# STM32H730_PINOUT.net
KiCad netlist of a schematic drawn in Altium Designer
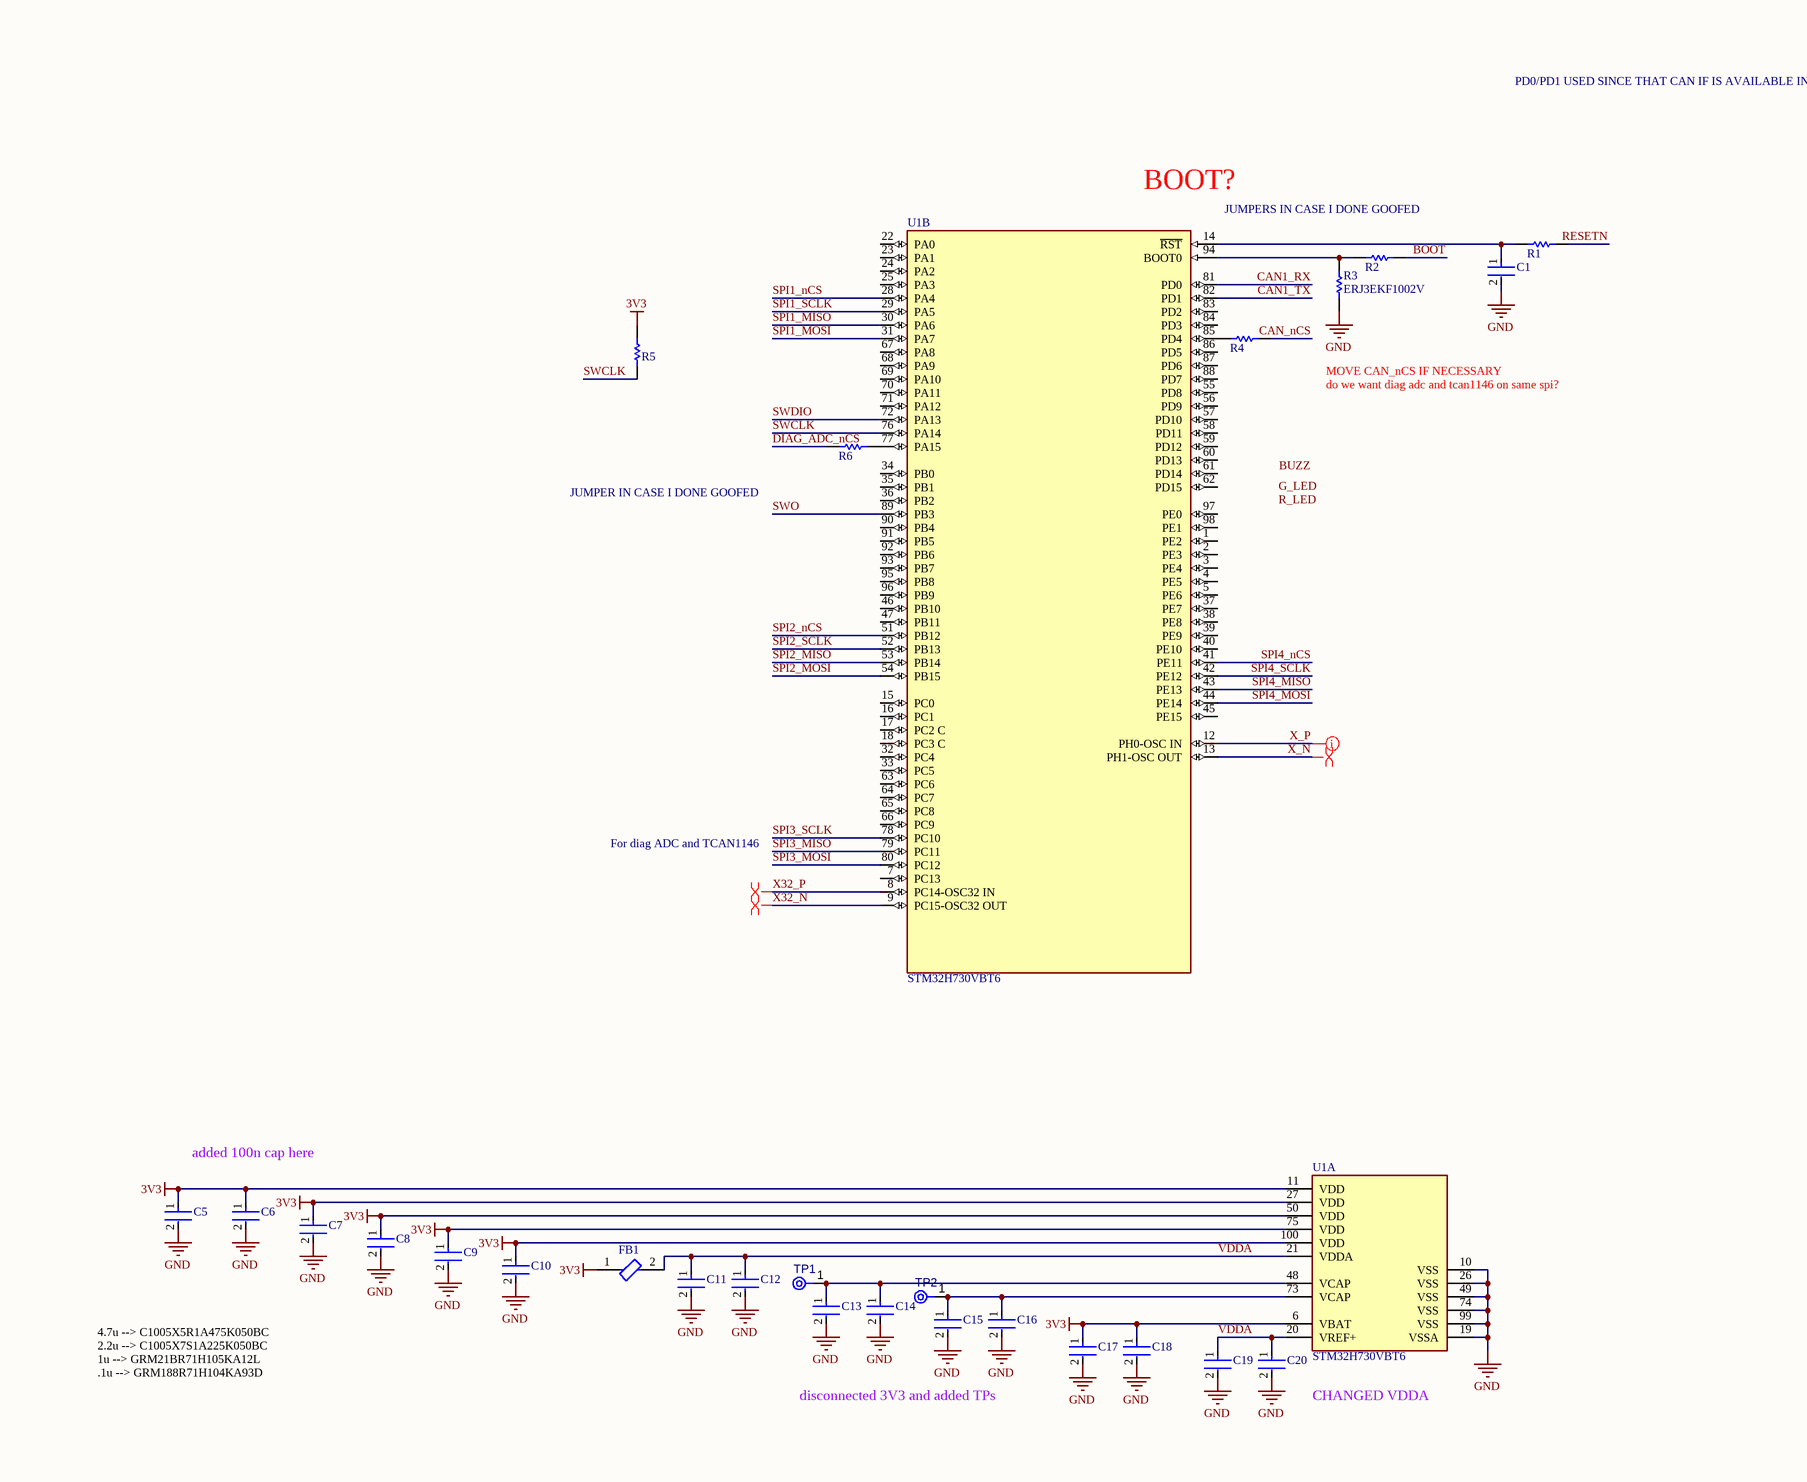
[diagram p0: STM32H730_PINOUT.SchDoc, top left]
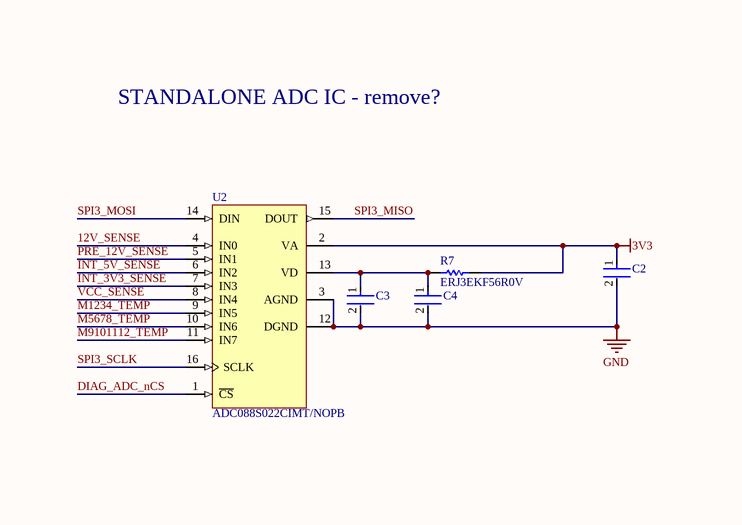
[diagram p1: STM32H730_PINOUT.SchDoc, top middle]
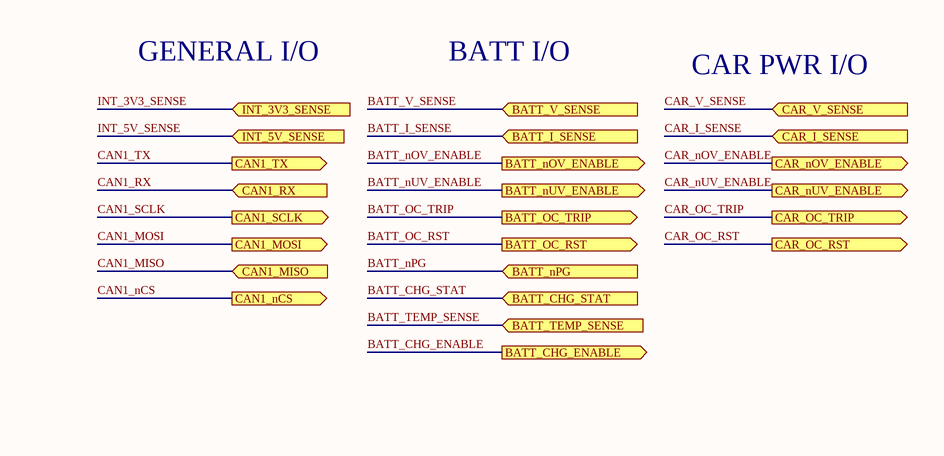
[diagram p2: STM32H730_PINOUT.SchDoc, top right]
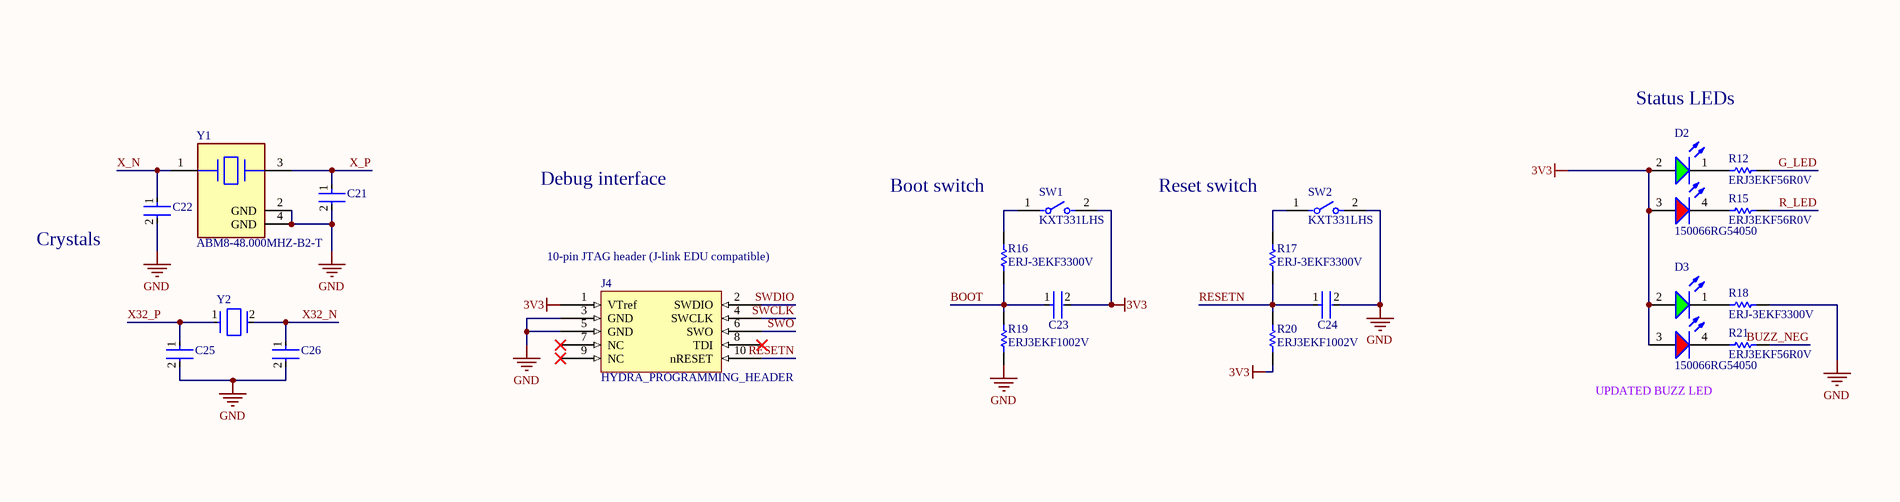
[diagram p3: STM32H730_PINOUT.SchDoc, bottom left]
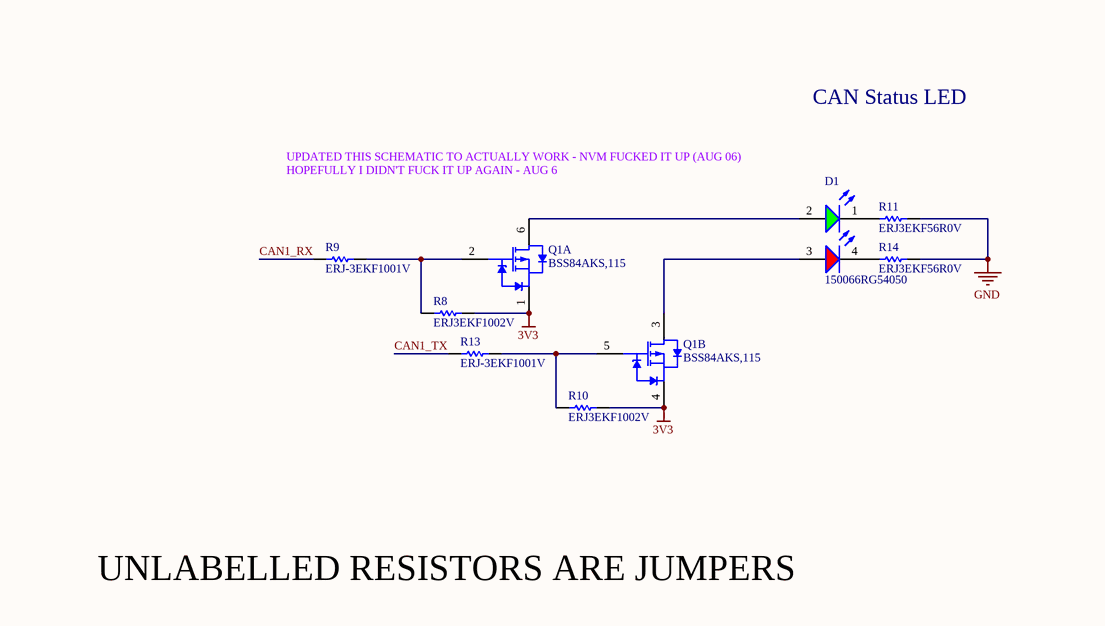
[diagram p4: STM32H730_PINOUT.SchDoc, bottom right]

(export (version "E")
  (design (tool "Eeschema 10.0.6"))
  (components
    (comp (ref "C1")
      (value "100n 10v")
      (footprint "FP-0402-L_1_0_0_05-W_0_5-IPC_A")
      (description "LARGE PADS, 0402 CAP, CHANGE COMMENT TO MATCH REAL P/N")
      (libsource (lib "Space Concordia") (part "b4654b650e69147ec39a6b967a45e02"))
    )
    (comp (ref "C2")
      (value "100n 10v")
      (footprint "FP-0402-L_1_0_0_05-W_0_5-IPC_A")
      (description "LARGE PADS, 0402 CAP, CHANGE COMMENT TO MATCH REAL P/N")
      (libsource (lib "Space Concordia") (part "b4654b650e69147ec39a6b967a45e02"))
    )
    (comp (ref "C3")
      (value "100n 10v")
      (footprint "FP-0402-L_1_0_0_05-W_0_5-IPC_A")
      (description "LARGE PADS, 0402 CAP, CHANGE COMMENT TO MATCH REAL P/N")
      (libsource (lib "Space Concordia") (part "b4654b650e69147ec39a6b967a45e02"))
    )
    (comp (ref "C4")
      (value "100n 10v")
      (footprint "FP-0402-L_1_0_0_05-W_0_5-IPC_A")
      (description "LARGE PADS, 0402 CAP, CHANGE COMMENT TO MATCH REAL P/N")
      (libsource (lib "Space Concordia") (part "b4654b650e69147ec39a6b967a45e02"))
    )
    (comp (ref "C5")
      (value "4.7u 10v")
      (footprint "FP-0402-L_1_0_0_05-W_0_5-IPC_A")
      (description "LARGE PADS, 0402 CAP, CHANGE COMMENT TO MATCH REAL P/N")
      (libsource (lib "Space Concordia") (part "b4654b650e69147ec39a6b967a45e02"))
    )
    (comp (ref "C6")
      (value "100n 10v")
      (footprint "FP-0402-L_1_0_0_05-W_0_5-IPC_A")
      (description "LARGE PADS, 0402 CAP, CHANGE COMMENT TO MATCH REAL P/N")
      (libsource (lib "Space Concordia") (part "b4654b650e69147ec39a6b967a45e02"))
    )
    (comp (ref "C7")
      (value "100n 10v")
      (footprint "FP-0402-L_1_0_0_05-W_0_5-IPC_A")
      (description "LARGE PADS, 0402 CAP, CHANGE COMMENT TO MATCH REAL P/N")
      (libsource (lib "Space Concordia") (part "b4654b650e69147ec39a6b967a45e02"))
    )
    (comp (ref "C8")
      (value "100n 10v")
      (footprint "FP-0402-L_1_0_0_05-W_0_5-IPC_A")
      (description "LARGE PADS, 0402 CAP, CHANGE COMMENT TO MATCH REAL P/N")
      (libsource (lib "Space Concordia") (part "b4654b650e69147ec39a6b967a45e02"))
    )
    (comp (ref "C9")
      (value "100n 10v")
      (footprint "FP-0402-L_1_0_0_05-W_0_5-IPC_A")
      (description "LARGE PADS, 0402 CAP, CHANGE COMMENT TO MATCH REAL P/N")
      (libsource (lib "Space Concordia") (part "b4654b650e69147ec39a6b967a45e02"))
    )
    (comp (ref "C10")
      (value "100n 10v")
      (footprint "FP-0402-L_1_0_0_05-W_0_5-IPC_A")
      (description "LARGE PADS, 0402 CAP, CHANGE COMMENT TO MATCH REAL P/N")
      (libsource (lib "Space Concordia") (part "b4654b650e69147ec39a6b967a45e02"))
    )
    (comp (ref "C11")
      (value "1u 10v")
      (footprint "FP-0402-L_1_0_0_05-W_0_5-IPC_A")
      (description "LARGE PADS, 0402 CAP, CHANGE COMMENT TO MATCH REAL P/N")
      (libsource (lib "Space Concordia") (part "b4654b650e69147ec39a6b967a45e02"))
    )
    (comp (ref "C12")
      (value "100n 10v")
      (footprint "FP-0402-L_1_0_0_05-W_0_5-IPC_A")
      (description "LARGE PADS, 0402 CAP, CHANGE COMMENT TO MATCH REAL P/N")
      (libsource (lib "Space Concordia") (part "b4654b650e69147ec39a6b967a45e02"))
    )
    (comp (ref "C13")
      (value "2.2u 10v")
      (footprint "FP-0402-L_1_0_0_05-W_0_5-IPC_A")
      (description "LARGE PADS, 0402 CAP, CHANGE COMMENT TO MATCH REAL P/N")
      (libsource (lib "Space Concordia") (part "b4654b650e69147ec39a6b967a45e02"))
    )
    (comp (ref "C14")
      (value "100n 10v")
      (footprint "FP-0402-L_1_0_0_05-W_0_5-IPC_A")
      (description "LARGE PADS, 0402 CAP, CHANGE COMMENT TO MATCH REAL P/N")
      (libsource (lib "Space Concordia") (part "b4654b650e69147ec39a6b967a45e02"))
    )
    (comp (ref "C15")
      (value "2.2u 10v")
      (footprint "FP-0402-L_1_0_0_05-W_0_5-IPC_A")
      (description "LARGE PADS, 0402 CAP, CHANGE COMMENT TO MATCH REAL P/N")
      (libsource (lib "Space Concordia") (part "b4654b650e69147ec39a6b967a45e02"))
    )
    (comp (ref "C16")
      (value "100n 10v")
      (footprint "FP-0402-L_1_0_0_05-W_0_5-IPC_A")
      (description "LARGE PADS, 0402 CAP, CHANGE COMMENT TO MATCH REAL P/N")
      (libsource (lib "Space Concordia") (part "b4654b650e69147ec39a6b967a45e02"))
    )
    (comp (ref "C17")
      (value "1u 10v")
      (footprint "FP-0402-L_1_0_0_05-W_0_5-IPC_A")
      (description "LARGE PADS, 0402 CAP, CHANGE COMMENT TO MATCH REAL P/N")
      (libsource (lib "Space Concordia") (part "b4654b650e69147ec39a6b967a45e02"))
    )
    (comp (ref "C18")
      (value "100n 10v")
      (footprint "FP-0402-L_1_0_0_05-W_0_5-IPC_A")
      (description "LARGE PADS, 0402 CAP, CHANGE COMMENT TO MATCH REAL P/N")
      (libsource (lib "Space Concordia") (part "b4654b650e69147ec39a6b967a45e02"))
    )
    (comp (ref "C19")
      (value "1u 10v")
      (footprint "FP-0402-L_1_0_0_05-W_0_5-IPC_A")
      (description "LARGE PADS, 0402 CAP, CHANGE COMMENT TO MATCH REAL P/N")
      (libsource (lib "Space Concordia") (part "b4654b650e69147ec39a6b967a45e02"))
    )
    (comp (ref "C20")
      (value "100n 10v")
      (footprint "FP-0402-L_1_0_0_05-W_0_5-IPC_A")
      (description "LARGE PADS, 0402 CAP, CHANGE COMMENT TO MATCH REAL P/N")
      (libsource (lib "Space Concordia") (part "b4654b650e69147ec39a6b967a45e02"))
    )
    (comp (ref "C21")
      (value "6.8p 10v")
      (footprint "FP-0402-L_1_0_0_05-W_0_5-IPC_A")
      (description "LARGE PADS, 0402 CAP, CHANGE COMMENT TO MATCH REAL P/N")
      (libsource (lib "Space Concordia") (part "b4654b650e69147ec39a6b967a45e02"))
    )
    (comp (ref "C22")
      (value "6.8p 10v")
      (footprint "FP-0402-L_1_0_0_05-W_0_5-IPC_A")
      (description "LARGE PADS, 0402 CAP, CHANGE COMMENT TO MATCH REAL P/N")
      (libsource (lib "Space Concordia") (part "b4654b650e69147ec39a6b967a45e02"))
    )
    (comp (ref "C23")
      (value "100n 10v")
      (footprint "FP-0402-L_1_0_0_05-W_0_5-IPC_A")
      (description "LARGE PADS, 0402 CAP, CHANGE COMMENT TO MATCH REAL P/N")
      (libsource (lib "Space Concordia") (part "b4654b650e69147ec39a6b967a45e02"))
    )
    (comp (ref "C24")
      (value "100n 10v")
      (footprint "FP-0402-L_1_0_0_05-W_0_5-IPC_A")
      (description "LARGE PADS, 0402 CAP, CHANGE COMMENT TO MATCH REAL P/N")
      (libsource (lib "Space Concordia") (part "b4654b650e69147ec39a6b967a45e02"))
    )
    (comp (ref "C25")
      (value "18pf 10v")
      (footprint "FP-0402-L_1_0_0_05-W_0_5-IPC_A")
      (description "LARGE PADS, 0402 CAP, CHANGE COMMENT TO MATCH REAL P/N")
      (libsource (lib "Space Concordia") (part "b4654b650e69147ec39a6b967a45e02"))
    )
    (comp (ref "C26")
      (value "18pf 10v")
      (footprint "FP-0402-L_1_0_0_05-W_0_5-IPC_A")
      (description "LARGE PADS, 0402 CAP, CHANGE COMMENT TO MATCH REAL P/N")
      (libsource (lib "Space Concordia") (part "b4654b650e69147ec39a6b967a45e02"))
    )
    (comp (ref "D1")
      (value "150066RG54050")
      (footprint "WL-SBCD_0606")
      (description "Led, Red/Grn, 180Mcd/230Mcd, 624Nm/525Nm Rohs Compliant: Yes")
      (libsource (lib "uORocketry Hardware") (part "WL-SBCD_0606_Red & Green"))
    )
    (comp (ref "D2")
      (value "150066RG54050")
      (footprint "WL-SBCD_0606")
      (description "Led, Red/Grn, 180Mcd/230Mcd, 624Nm/525Nm Rohs Compliant: Yes")
      (libsource (lib "uORocketry Hardware") (part "WL-SBCD_0606_Red & Green"))
    )
    (comp (ref "D3")
      (value "150066RG54050")
      (footprint "WL-SBCD_0606")
      (description "Led, Red/Grn, 180Mcd/230Mcd, 624Nm/525Nm Rohs Compliant: Yes")
      (libsource (lib "uORocketry Hardware") (part "WL-SBCD_0606_Red & Green"))
    )
    (comp (ref "FB1")
      (value "BLM15PX601SN1D")
      (footprint "FP-BLM15-0_05-MFG")
      (description "Chip Ferrite Bead, 0402, 600Ω @ 100MHz, 0.23Ω, 25%, 900mA")
      (fields (field (name "TOLERANCE") "25%"))
      (libsource (lib "Altium Content Vault") (part "5f30dd21d616792df468990f7003faa"))
    )
    (comp (ref "J4")
      (value "HYDRA_PROGRAMMING_HEADER")
      (footprint "3220-10-0300-00-Footprint-1")
      (description "CONN HEADER SMD 10POS 1.27MM (specifically compatible with J-Link EDU cable) PN: 3220-10-0300-00")
      (libsource (lib "uORocketry Hardware") (part "3220-10-0300-00-Symbol-1"))
    )
    (comp (ref "Q1")
      (value "BSS84AKS,115")
      (footprint "NXP-SOT363_L")
      (description "Dual P-Channel Trench MOSFET, -50 V, -0.16 A, -55 to 150 degC, 6-Pin SOT363, Tape and Reel")
      (fields (field (name "MANUFACTURER") "NXP Semiconductors"))
      (libsource (lib "Altium Content Vault") (part "NXP-PPMOS-SGDSGD-6_A"))
    )
    (comp (ref "R1")
      (value "0402 JUMPER 0 OHM")
      (footprint "RESC1005X40X25NL05T05")
      (description "READ THE NAME")
      (libsource (lib "uORocketry Hardware") (part "RES"))
    )
    (comp (ref "R2")
      (value "0402 JUMPER 0 OHM")
      (footprint "RESC1005X40X25NL05T05")
      (description "READ THE NAME")
      (libsource (lib "uORocketry Hardware") (part "RES"))
    )
    (comp (ref "R3")
      (value "ERJ3EKF1002V")
      (footprint "RESC1609X55X30LL15T15")
      (description "Chip Resistor, 10 KOhm, +/- 1%, 0.1 W, -55 to 155 degC, 0603 (1608 Metric), RoHS, Tape and Reel")
      (fields (field (name "TOLERANCE") "1%") (field (name "MANUFACTURER") "Panasonic"))
      (libsource (lib "Altium Content Vault") (part "RES-2"))
    )
    (comp (ref "R4")
      (value "0402 JUMPER 0 OHM")
      (footprint "RESC1005X40X25NL05T05")
      (description "READ THE NAME")
      (libsource (lib "uORocketry Hardware") (part "RES"))
    )
    (comp (ref "R5")
      (value "ERJ3EKF1002V")
      (footprint "RESC1609X55X30LL15T15")
      (description "Chip Resistor, 10 KOhm, +/- 1%, 0.1 W, -55 to 155 degC, 0603 (1608 Metric), RoHS, Tape and Reel")
      (fields (field (name "TOLERANCE") "1%") (field (name "MANUFACTURER") "Panasonic"))
      (libsource (lib "Altium Content Vault") (part "RES-2"))
    )
    (comp (ref "R6")
      (value "0402 JUMPER 0 OHM")
      (footprint "RESC1005X40X25NL05T05")
      (description "READ THE NAME")
      (libsource (lib "uORocketry Hardware") (part "RES"))
    )
    (comp (ref "R7")
      (value "ERJ3EKF56R0V")
      (footprint "RESC1608X55X30NL15T15")
      (fields (field (name "MANUFACTURER") "Panasonic"))
      (libsource (lib "Altium Content Vault") (part "RES"))
    )
    (comp (ref "R8")
      (value "ERJ3EKF1002V")
      (footprint "RESC1609X55X30LL15T15")
      (description "Chip Resistor, 10 KOhm, +/- 1%, 0.1 W, -55 to 155 degC, 0603 (1608 Metric), RoHS, Tape and Reel")
      (fields (field (name "TOLERANCE") "1%") (field (name "MANUFACTURER") "Panasonic"))
      (libsource (lib "Altium Content Vault") (part "RES-2"))
    )
    (comp (ref "R9")
      (value "ERJ-3EKF1001V")
      (footprint "RESC1608X55X30LL15T15")
      (fields (field (name "MANUFACTURER") "Panasonic"))
      (libsource (lib "Altium Content Vault") (part "RES"))
    )
    (comp (ref "R10")
      (value "ERJ3EKF1002V")
      (footprint "RESC1609X55X30LL15T15")
      (description "Chip Resistor, 10 KOhm, +/- 1%, 0.1 W, -55 to 155 degC, 0603 (1608 Metric), RoHS, Tape and Reel")
      (fields (field (name "TOLERANCE") "1%") (field (name "MANUFACTURER") "Panasonic"))
      (libsource (lib "Altium Content Vault") (part "RES-2"))
    )
    (comp (ref "R11")
      (value "ERJ3EKF56R0V")
      (footprint "RESC1608X55X30NL15T15")
      (fields (field (name "MANUFACTURER") "Panasonic"))
      (libsource (lib "Altium Content Vault") (part "RES"))
    )
    (comp (ref "R12")
      (value "ERJ3EKF56R0V")
      (footprint "RESC1608X55X30NL15T15")
      (fields (field (name "MANUFACTURER") "Panasonic"))
      (libsource (lib "Altium Content Vault") (part "RES"))
    )
    (comp (ref "R13")
      (value "ERJ-3EKF1001V")
      (footprint "RESC1608X55X30LL15T15")
      (fields (field (name "MANUFACTURER") "Panasonic"))
      (libsource (lib "Altium Content Vault") (part "RES"))
    )
    (comp (ref "R14")
      (value "ERJ3EKF56R0V")
      (footprint "RESC1608X55X30NL15T15")
      (fields (field (name "MANUFACTURER") "Panasonic"))
      (libsource (lib "Altium Content Vault") (part "RES"))
    )
    (comp (ref "R15")
      (value "ERJ3EKF56R0V")
      (footprint "RESC1608X55X30NL15T15")
      (fields (field (name "MANUFACTURER") "Panasonic"))
      (libsource (lib "Altium Content Vault") (part "RES"))
    )
    (comp (ref "R16")
      (value "ERJ-3EKF3300V")
      (footprint "RESC1608X55X30LL15T15")
      (description "Chip Resistor, 330 Ohm, +/- 1%, 0.1 W, -55 to 155 degC, 0603 (1608 Metric), RoHS, Tape and Reel")
      (libsource (lib "Altium Content Vault") (part "RES-2"))
    )
    (comp (ref "R17")
      (value "ERJ-3EKF3300V")
      (footprint "RESC1608X55X30LL15T15")
      (description "Chip Resistor, 330 Ohm, +/- 1%, 0.1 W, -55 to 155 degC, 0603 (1608 Metric), RoHS, Tape and Reel")
      (libsource (lib "Altium Content Vault") (part "RES-2"))
    )
    (comp (ref "R18")
      (value "ERJ-3EKF3300V")
      (footprint "RESC1608X55X30LL15T15")
      (description "Chip Resistor, 330 Ohm, +/- 1%, 0.1 W, -55 to 155 degC, 0603 (1608 Metric), RoHS, Tape and Reel")
      (libsource (lib "Altium Content Vault") (part "RES-2"))
    )
    (comp (ref "R19")
      (value "ERJ3EKF1002V")
      (footprint "RESC1609X55X30LL15T15")
      (description "Chip Resistor, 10 KOhm, +/- 1%, 0.1 W, -55 to 155 degC, 0603 (1608 Metric), RoHS, Tape and Reel")
      (fields (field (name "TOLERANCE") "1%") (field (name "MANUFACTURER") "Panasonic"))
      (libsource (lib "Altium Content Vault") (part "RES-2"))
    )
    (comp (ref "R20")
      (value "ERJ3EKF1002V")
      (footprint "RESC1609X55X30LL15T15")
      (description "Chip Resistor, 10 KOhm, +/- 1%, 0.1 W, -55 to 155 degC, 0603 (1608 Metric), RoHS, Tape and Reel")
      (fields (field (name "TOLERANCE") "1%") (field (name "MANUFACTURER") "Panasonic"))
      (libsource (lib "Altium Content Vault") (part "RES-2"))
    )
    (comp (ref "R21")
      (value "ERJ3EKF56R0V")
      (footprint "RESC1608X55X30NL15T15")
      (fields (field (name "MANUFACTURER") "Panasonic"))
      (libsource (lib "Altium Content Vault") (part "RES"))
    )
    (comp (ref "SW1")
      (value "KXT331LHS")
      (footprint "FP-KXT331LHS-MFG")
      (description "SWITCH TACTILE SPST-NO 0.02A 15V")
      (libsource (lib "Altium Content Vault") (part "bb27bde45df87f1f469753f287ef5ae"))
    )
    (comp (ref "SW2")
      (value "KXT331LHS")
      (footprint "FP-KXT331LHS-MFG")
      (description "SWITCH TACTILE SPST-NO 0.02A 15V")
      (libsource (lib "Altium Content Vault") (part "bb27bde45df87f1f469753f287ef5ae"))
    )
    (comp (ref "TP1")
      (value "TPAD6R")
      (footprint "TP06R")
      (description "0.6mm round")
      (libsource (lib "uORocketry Hardware") (part "CMP-001-0001-4"))
    )
    (comp (ref "TP2")
      (value "TPAD6R")
      (footprint "TP06R")
      (description "0.6mm round")
      (libsource (lib "uORocketry Hardware") (part "CMP-001-0001-4"))
    )
    (comp (ref "U1")
      (value "STM32H730VBT6")
      (footprint "FP-LQFP100-1L-IPC_C")
      (description "IC MCU 32BIT 128KB FLASH 100LQFP")
      (libsource (lib "Altium Content Vault") (part "44dc6501260a4d92b846760feb66c20"))
    )
    (comp (ref "U2")
      (value "ADC088S022CIMT/NOPB")
      (footprint "MTC16_L")
      (description "8-Channel, 50 kSPS to 200 kSPS, 8-Bit A/D Converter, 16-pin TSSOP, Pb-Free")
      (fields (field (name "MANUFACTURER") "National Semiconductor"))
      (libsource (lib "Altium Content Vault") (part "CON-ADC-ADC108S052CIMT"))
    )
    (comp (ref "Y1")
      (value "ABM8-48.000MHZ-B2-T")
      (footprint "FP-ABM8-MFG")
      (description "Crystal 48MHz ±20ppm 18pF SMD-4 3.2mm x 2.5mm")
      (fields (field (name "TOLERANCE") "20ppm"))
      (libsource (lib "Altium Content Vault") (part "dfdb7f9a12507849fb681da9a70121c"))
    )
    (comp (ref "Y2")
      (value "ECS-.327-12.5-1210-TR")
      (footprint "FP-ECX-1210-MFG")
      (description "CRYSTAL 32.7680KHZ 12.5PF SMD")
      (fields
        (field (name "OCTOPART") "https://octopart.com/ecs-.327-12.5-1210-tr-ecs+international-81221340")
        (field (name "TOLERANCE") "20ppm")
      )
      (libsource (lib "Altium Content Vault") (part "99724985039315a44fd0d1401b84e49"))
    )
  )
  (nets
    (net (code "1") (name "/12V_SENSE") (class "Default")
      (node (ref "U2") (pin "4") (pinfunction "IN0_4") (pintype "input"))
    )
    (net (code "12") (name "/BOOT") (class "Default")
      (node (ref "C23") (pin "1") (pinfunction "1_1") (pintype "passive"))
      (node (ref "R16") (pin "1") (pinfunction "1_1") (pintype "passive"))
      (node (ref "R19") (pin "2") (pinfunction "2_2") (pintype "passive"))
      (node (ref "R2") (pin "2") (pinfunction "2_2") (pintype "passive"))
    )
    (net (code "14") (name "/BUZZ_NEG") (class "Default")
      (node (ref "R21") (pin "1") (pinfunction "1_1") (pintype "passive"))
    )
    (net (code "17") (name "/CAN1_RX") (class "Default")
      (node (ref "R9") (pin "1") (pinfunction "1_1") (pintype "passive"))
      (node (ref "U1") (pin "81") (pinfunction "PD0_81") (pintype "bidirectional"))
    )
    (net (code "19") (name "/CAN1_TX") (class "Default")
      (node (ref "R13") (pin "1") (pinfunction "1_1") (pintype "passive"))
      (node (ref "U1") (pin "82") (pinfunction "PD1_82") (pintype "bidirectional"))
    )
    (net (code "21") (name "/CAN_nCS") (class "Default")
      (node (ref "R4") (pin "2") (pinfunction "2_2") (pintype "passive"))
    )
    (net (code "28") (name "/DIAG_ADC_nCS") (class "Default")
      (node (ref "R6") (pin "1") (pinfunction "1_1") (pintype "passive"))
      (node (ref "U2") (pin "1") (pinfunction "~{CS}_1") (pintype "input"))
    )
    (net (code "29") (name "/G_LED") (class "Default")
      (node (ref "R12") (pin "1") (pinfunction "1_1") (pintype "passive"))
    )
    (net (code "30") (name "/INT_3V3_SENSE") (class "Default")
      (node (ref "U2") (pin "7") (pinfunction "IN3_7") (pintype "input"))
    )
    (net (code "31") (name "/INT_5V_SENSE") (class "Default")
      (node (ref "U2") (pin "6") (pinfunction "IN2_6") (pintype "input"))
    )
    (net (code "32") (name "/M1234_TEMP") (class "Default")
      (node (ref "U2") (pin "9") (pinfunction "IN5_9") (pintype "input"))
    )
    (net (code "33") (name "/M5678_TEMP") (class "Default")
      (node (ref "U2") (pin "10") (pinfunction "IN6_10") (pintype "input"))
    )
    (net (code "34") (name "/M9101112_TEMP") (class "Default")
      (node (ref "U2") (pin "11") (pinfunction "IN7_11") (pintype "input"))
    )
    (net (code "35") (name "/PRE_12V_SENSE") (class "Default")
      (node (ref "U2") (pin "5") (pinfunction "IN1_5") (pintype "input"))
    )
    (net (code "36") (name "/RESETN") (class "Default")
      (node (ref "C24") (pin "1") (pinfunction "1_1") (pintype "passive"))
      (node (ref "J4") (pin "10") (pinfunction "nRESET_10") (pintype "input"))
      (node (ref "R1") (pin "2") (pinfunction "2_2") (pintype "passive"))
      (node (ref "R17") (pin "1") (pinfunction "1_1") (pintype "passive"))
      (node (ref "R20") (pin "2") (pinfunction "2_2") (pintype "passive"))
    )
    (net (code "37") (name "/R_LED") (class "Default")
      (node (ref "R15") (pin "1") (pinfunction "1_1") (pintype "passive"))
    )
    (net (code "38") (name "/SPI1_MISO") (class "Default")
      (node (ref "U1") (pin "30") (pinfunction "PA6_30") (pintype "bidirectional"))
    )
    (net (code "39") (name "/SPI1_MOSI") (class "Default")
      (node (ref "U1") (pin "31") (pinfunction "PA7_31") (pintype "bidirectional"))
    )
    (net (code "40") (name "/SPI1_SCLK") (class "Default")
      (node (ref "U1") (pin "29") (pinfunction "PA5_29") (pintype "bidirectional"))
    )
    (net (code "41") (name "/SPI1_nCS") (class "Default")
      (node (ref "U1") (pin "28") (pinfunction "PA4_28") (pintype "bidirectional"))
    )
    (net (code "42") (name "/SPI2_MISO") (class "Default")
      (node (ref "U1") (pin "53") (pinfunction "PB14_53") (pintype "bidirectional"))
    )
    (net (code "43") (name "/SPI2_MOSI") (class "Default")
      (node (ref "U1") (pin "54") (pinfunction "PB15_54") (pintype "bidirectional"))
    )
    (net (code "44") (name "/SPI2_SCLK") (class "Default")
      (node (ref "U1") (pin "52") (pinfunction "PB13_52") (pintype "bidirectional"))
    )
    (net (code "45") (name "/SPI2_nCS") (class "Default")
      (node (ref "U1") (pin "51") (pinfunction "PB12_51") (pintype "bidirectional"))
    )
    (net (code "46") (name "/SPI3_MISO") (class "Default")
      (node (ref "U1") (pin "79") (pinfunction "PC11_79") (pintype "bidirectional"))
      (node (ref "U2") (pin "15") (pinfunction "DOUT_15") (pintype "output"))
    )
    (net (code "47") (name "/SPI3_MOSI") (class "Default")
      (node (ref "U1") (pin "80") (pinfunction "PC12_80") (pintype "bidirectional"))
      (node (ref "U2") (pin "14") (pinfunction "DIN_14") (pintype "input"))
    )
    (net (code "48") (name "/SPI3_SCLK") (class "Default")
      (node (ref "U1") (pin "78") (pinfunction "PC10_78") (pintype "bidirectional"))
      (node (ref "U2") (pin "16") (pinfunction "SCLK_16") (pintype "input"))
    )
    (net (code "49") (name "/SPI4_MISO") (class "Default")
      (node (ref "U1") (pin "43") (pinfunction "PE13_43") (pintype "bidirectional"))
    )
    (net (code "50") (name "/SPI4_MOSI") (class "Default")
      (node (ref "U1") (pin "44") (pinfunction "PE14_44") (pintype "bidirectional"))
    )
    (net (code "51") (name "/SPI4_SCLK") (class "Default")
      (node (ref "U1") (pin "42") (pinfunction "PE12_42") (pintype "bidirectional"))
    )
    (net (code "52") (name "/SPI4_nCS") (class "Default")
      (node (ref "U1") (pin "41") (pinfunction "PE11_41") (pintype "bidirectional"))
    )
    (net (code "53") (name "/SWCLK") (class "Default")
      (node (ref "J4") (pin "4") (pinfunction "SWCLK_4") (pintype "input"))
      (node (ref "R5") (pin "2") (pinfunction "2_2") (pintype "passive"))
      (node (ref "U1") (pin "76") (pinfunction "PA14_76") (pintype "bidirectional"))
    )
    (net (code "54") (name "/SWDIO") (class "Default")
      (node (ref "J4") (pin "2") (pinfunction "SWDIO_2") (pintype "input"))
      (node (ref "U1") (pin "72") (pinfunction "PA13_72") (pintype "bidirectional"))
    )
    (net (code "55") (name "/SWO") (class "Default")
      (node (ref "J4") (pin "6") (pinfunction "SWO_6") (pintype "input"))
      (node (ref "U1") (pin "89") (pinfunction "PB3_89") (pintype "bidirectional"))
    )
    (net (code "56") (name "/VCC_SENSE") (class "Default")
      (node (ref "U2") (pin "8") (pinfunction "IN4_8") (pintype "input"))
    )
    (net (code "57") (name "/VDDA") (class "Default")
      (node (ref "C11") (pin "1") (pinfunction "1_1") (pintype "passive"))
      (node (ref "C12") (pin "1") (pinfunction "1_1") (pintype "passive"))
      (node (ref "C19") (pin "1") (pinfunction "1_1") (pintype "passive"))
      (node (ref "C20") (pin "1") (pinfunction "1_1") (pintype "passive"))
      (node (ref "FB1") (pin "2") (pinfunction "2_2") (pintype "passive"))
      (node (ref "U1") (pin "20") (pinfunction "VREF+_20") (pintype "power_in"))
      (node (ref "U1") (pin "21") (pinfunction "VDDA_21") (pintype "power_in"))
    )
    (net (code "58") (name "/X32_N") (class "Default")
      (node (ref "C26") (pin "1") (pinfunction "1_1") (pintype "passive"))
      (node (ref "U1") (pin "9") (pinfunction "PC15-OSC32_OUT_9") (pintype "bidirectional"))
      (node (ref "Y2") (pin "2") (pinfunction "Out/In_2") (pintype "passive"))
    )
    (net (code "59") (name "/X32_P") (class "Default")
      (node (ref "C25") (pin "1") (pinfunction "1_1") (pintype "passive"))
      (node (ref "U1") (pin "8") (pinfunction "PC14-OSC32_IN_8") (pintype "bidirectional"))
      (node (ref "Y2") (pin "1") (pinfunction "In/Out_1") (pintype "passive"))
    )
    (net (code "60") (name "/X_N") (class "Default")
      (node (ref "C22") (pin "1") (pinfunction "1_1") (pintype "passive"))
      (node (ref "U1") (pin "13") (pinfunction "PH1-OSC_OUT_13") (pintype "bidirectional"))
      (node (ref "Y1") (pin "1") (pinfunction "1_1") (pintype "passive"))
    )
    (net (code "61") (name "/X_P") (class "Default")
      (node (ref "C21") (pin "1") (pinfunction "1_1") (pintype "passive"))
      (node (ref "U1") (pin "12") (pinfunction "PH0-OSC_IN_12") (pintype "bidirectional"))
      (node (ref "Y1") (pin "3") (pinfunction "3_3") (pintype "passive"))
    )
    (net (code "62") (name "3V3") (class "Default")
      (node (ref "C10") (pin "1") (pinfunction "1_1") (pintype "passive"))
      (node (ref "C17") (pin "1") (pinfunction "1_1") (pintype "passive"))
      (node (ref "C18") (pin "1") (pinfunction "1_1") (pintype "passive"))
      (node (ref "C2") (pin "1") (pinfunction "1_1") (pintype "passive"))
      (node (ref "C23") (pin "2") (pinfunction "2_2") (pintype "passive"))
      (node (ref "C5") (pin "1") (pinfunction "1_1") (pintype "passive"))
      (node (ref "C6") (pin "1") (pinfunction "1_1") (pintype "passive"))
      (node (ref "C7") (pin "1") (pinfunction "1_1") (pintype "passive"))
      (node (ref "C8") (pin "1") (pinfunction "1_1") (pintype "passive"))
      (node (ref "C9") (pin "1") (pinfunction "1_1") (pintype "passive"))
      (node (ref "D2") (pin "2") (pinfunction "A_2") (pintype "passive"))
      (node (ref "D2") (pin "3") (pinfunction "A_3") (pintype "passive"))
      (node (ref "D3") (pin "2") (pinfunction "A_2") (pintype "passive"))
      (node (ref "D3") (pin "3") (pinfunction "A_3") (pintype "passive"))
      (node (ref "FB1") (pin "1") (pinfunction "1_1") (pintype "passive"))
      (node (ref "J4") (pin "1") (pinfunction "VTref_1") (pintype "input"))
      (node (ref "Q1") (pin "1") (pinfunction "S1_1") (pintype "passive"))
      (node (ref "Q1") (pin "4") (pinfunction "S2_4") (pintype "passive"))
      (node (ref "R10") (pin "2") (pinfunction "2_2") (pintype "passive"))
      (node (ref "R20") (pin "1") (pinfunction "1_1") (pintype "passive"))
      (node (ref "R5") (pin "1") (pinfunction "1_1") (pintype "passive"))
      (node (ref "R7") (pin "1") (pinfunction "1_1") (pintype "passive"))
      (node (ref "R8") (pin "2") (pinfunction "2_2") (pintype "passive"))
      (node (ref "SW1") (pin "2") (pinfunction "2_2") (pintype "passive"))
      (node (ref "U1") (pin "100") (pinfunction "VDD_100") (pintype "power_in"))
      (node (ref "U1") (pin "11") (pinfunction "VDD_11") (pintype "power_in"))
      (node (ref "U1") (pin "27") (pinfunction "VDD_27") (pintype "power_in"))
      (node (ref "U1") (pin "50") (pinfunction "VDD_50") (pintype "power_in"))
      (node (ref "U1") (pin "6") (pinfunction "VBAT_6") (pintype "power_in"))
      (node (ref "U1") (pin "75") (pinfunction "VDD_75") (pintype "power_in"))
      (node (ref "U2") (pin "2") (pinfunction "VA_2") (pintype "power_in"))
    )
    (net (code "63") (name "GND") (class "Default")
      (node (ref "C1") (pin "2") (pinfunction "2_2") (pintype "passive"))
      (node (ref "C10") (pin "2") (pinfunction "2_2") (pintype "passive"))
      (node (ref "C11") (pin "2") (pinfunction "2_2") (pintype "passive"))
      (node (ref "C12") (pin "2") (pinfunction "2_2") (pintype "passive"))
      (node (ref "C13") (pin "2") (pinfunction "2_2") (pintype "passive"))
      (node (ref "C14") (pin "2") (pinfunction "2_2") (pintype "passive"))
      (node (ref "C15") (pin "2") (pinfunction "2_2") (pintype "passive"))
      (node (ref "C16") (pin "2") (pinfunction "2_2") (pintype "passive"))
      (node (ref "C17") (pin "2") (pinfunction "2_2") (pintype "passive"))
      (node (ref "C18") (pin "2") (pinfunction "2_2") (pintype "passive"))
      (node (ref "C19") (pin "2") (pinfunction "2_2") (pintype "passive"))
      (node (ref "C2") (pin "2") (pinfunction "2_2") (pintype "passive"))
      (node (ref "C20") (pin "2") (pinfunction "2_2") (pintype "passive"))
      (node (ref "C21") (pin "2") (pinfunction "2_2") (pintype "passive"))
      (node (ref "C22") (pin "2") (pinfunction "2_2") (pintype "passive"))
      (node (ref "C24") (pin "2") (pinfunction "2_2") (pintype "passive"))
      (node (ref "C25") (pin "2") (pinfunction "2_2") (pintype "passive"))
      (node (ref "C26") (pin "2") (pinfunction "2_2") (pintype "passive"))
      (node (ref "C3") (pin "2") (pinfunction "2_2") (pintype "passive"))
      (node (ref "C4") (pin "2") (pinfunction "2_2") (pintype "passive"))
      (node (ref "C5") (pin "2") (pinfunction "2_2") (pintype "passive"))
      (node (ref "C6") (pin "2") (pinfunction "2_2") (pintype "passive"))
      (node (ref "C7") (pin "2") (pinfunction "2_2") (pintype "passive"))
      (node (ref "C8") (pin "2") (pinfunction "2_2") (pintype "passive"))
      (node (ref "C9") (pin "2") (pinfunction "2_2") (pintype "passive"))
      (node (ref "J4") (pin "3") (pinfunction "GND_3") (pintype "input"))
      (node (ref "J4") (pin "5") (pinfunction "GND_5") (pintype "input"))
      (node (ref "R11") (pin "1") (pinfunction "1_1") (pintype "passive"))
      (node (ref "R14") (pin "1") (pinfunction "1_1") (pintype "passive"))
      (node (ref "R18") (pin "2") (pinfunction "2_2") (pintype "passive"))
      (node (ref "R19") (pin "1") (pinfunction "1_1") (pintype "passive"))
      (node (ref "R3") (pin "1") (pinfunction "1_1") (pintype "passive"))
      (node (ref "SW2") (pin "2") (pinfunction "2_2") (pintype "passive"))
      (node (ref "U1") (pin "10") (pinfunction "VSS_10") (pintype "power_in"))
      (node (ref "U1") (pin "19") (pinfunction "VSSA_19") (pintype "power_in"))
      (node (ref "U1") (pin "26") (pinfunction "VSS_26") (pintype "power_in"))
      (node (ref "U1") (pin "49") (pinfunction "VSS_49") (pintype "power_in"))
      (node (ref "U1") (pin "74") (pinfunction "VSS_74") (pintype "power_in"))
      (node (ref "U1") (pin "99") (pinfunction "VSS_99") (pintype "power_in"))
      (node (ref "U2") (pin "12") (pinfunction "DGND_12") (pintype "power_in"))
      (node (ref "U2") (pin "3") (pinfunction "AGND_3") (pintype "power_in"))
      (node (ref "Y1") (pin "2") (pinfunction "GND_2") (pintype "power_in"))
      (node (ref "Y1") (pin "4") (pinfunction "GND_4") (pintype "power_in"))
    )
    (net (code "64") (name "Net-(D1-K-Pad1)") (class "Default")
      (node (ref "D1") (pin "1") (pinfunction "K_1") (pintype "passive"))
      (node (ref "R11") (pin "2") (pinfunction "2_2") (pintype "passive"))
    )
    (net (code "65") (name "Net-(D1-K-Pad4)") (class "Default")
      (node (ref "D1") (pin "4") (pinfunction "K_4") (pintype "passive"))
      (node (ref "R14") (pin "2") (pinfunction "2_2") (pintype "passive"))
    )
    (net (code "66") (name "Net-(D2-K-Pad1)") (class "Default")
      (node (ref "D2") (pin "1") (pinfunction "K_1") (pintype "passive"))
      (node (ref "R12") (pin "2") (pinfunction "2_2") (pintype "passive"))
    )
    (net (code "67") (name "Net-(D2-K-Pad4)") (class "Default")
      (node (ref "D2") (pin "4") (pinfunction "K_4") (pintype "passive"))
      (node (ref "R15") (pin "2") (pinfunction "2_2") (pintype "passive"))
    )
    (net (code "68") (name "Net-(D3-K-Pad1)") (class "Default")
      (node (ref "D3") (pin "1") (pinfunction "K_1") (pintype "passive"))
      (node (ref "R18") (pin "1") (pinfunction "1_1") (pintype "passive"))
    )
    (net (code "69") (name "Net-(D3-K-Pad4)") (class "Default")
      (node (ref "D3") (pin "4") (pinfunction "K_4") (pintype "passive"))
      (node (ref "R21") (pin "2") (pinfunction "2_2") (pintype "passive"))
    )
    (net (code "70") (name "Net-(Q1A-D1)") (class "Default")
      (node (ref "D1") (pin "2") (pinfunction "A_2") (pintype "passive"))
      (node (ref "Q1") (pin "6") (pinfunction "D1_6") (pintype "passive"))
    )
    (net (code "71") (name "Net-(Q1A-G1)") (class "Default")
      (node (ref "Q1") (pin "2") (pinfunction "G1_2") (pintype "passive"))
      (node (ref "R8") (pin "1") (pinfunction "1_1") (pintype "passive"))
      (node (ref "R9") (pin "2") (pinfunction "2_2") (pintype "passive"))
    )
    (net (code "72") (name "Net-(Q1B-D2)") (class "Default")
      (node (ref "D1") (pin "3") (pinfunction "A_3") (pintype "passive"))
      (node (ref "Q1") (pin "3") (pinfunction "D2_3") (pintype "passive"))
    )
    (net (code "73") (name "Net-(Q1B-G2)") (class "Default")
      (node (ref "Q1") (pin "5") (pinfunction "G2_5") (pintype "passive"))
      (node (ref "R10") (pin "1") (pinfunction "1_1") (pintype "passive"))
      (node (ref "R13") (pin "2") (pinfunction "2_2") (pintype "passive"))
    )
    (net (code "74") (name "Net-(R16-Pad2)") (class "Default")
      (node (ref "R16") (pin "2") (pinfunction "2_2") (pintype "passive"))
      (node (ref "SW1") (pin "1") (pinfunction "1_1") (pintype "passive"))
    )
    (net (code "75") (name "Net-(R17-Pad2)") (class "Default")
      (node (ref "R17") (pin "2") (pinfunction "2_2") (pintype "passive"))
      (node (ref "SW2") (pin "1") (pinfunction "1_1") (pintype "passive"))
    )
    (net (code "76") (name "Net-(TP1-TP)") (class "Default")
      (node (ref "C13") (pin "1") (pinfunction "1_1") (pintype "passive"))
      (node (ref "C14") (pin "1") (pinfunction "1_1") (pintype "passive"))
      (node (ref "TP1") (pin "1") (pinfunction "TP_1") (pintype "passive"))
      (node (ref "U1") (pin "48") (pinfunction "VCAP_48") (pintype "power_in"))
    )
    (net (code "77") (name "Net-(TP2-TP)") (class "Default")
      (node (ref "C15") (pin "1") (pinfunction "1_1") (pintype "passive"))
      (node (ref "C16") (pin "1") (pinfunction "1_1") (pintype "passive"))
      (node (ref "TP2") (pin "1") (pinfunction "TP_1") (pintype "passive"))
      (node (ref "U1") (pin "73") (pinfunction "VCAP_73") (pintype "power_in"))
    )
    (net (code "78") (name "Net-(U1B-BOOT0)") (class "Default")
      (node (ref "R2") (pin "1") (pinfunction "1_1") (pintype "passive"))
      (node (ref "R3") (pin "2") (pinfunction "2_2") (pintype "passive"))
      (node (ref "U1") (pin "94") (pinfunction "BOOT0_94") (pintype "input"))
    )
    (net (code "79") (name "Net-(U1B-PA15)") (class "Default")
      (node (ref "R6") (pin "2") (pinfunction "2_2") (pintype "passive"))
      (node (ref "U1") (pin "77") (pinfunction "PA15_77") (pintype "bidirectional"))
    )
    (net (code "80") (name "Net-(U1B-PD4)") (class "Default")
      (node (ref "R4") (pin "1") (pinfunction "1_1") (pintype "passive"))
      (node (ref "U1") (pin "85") (pinfunction "PD4_85") (pintype "bidirectional"))
    )
    (net (code "81") (name "Net-(U1B-~{RST})") (class "Default")
      (node (ref "C1") (pin "1") (pinfunction "1_1") (pintype "passive"))
      (node (ref "R1") (pin "1") (pinfunction "1_1") (pintype "passive"))
      (node (ref "U1") (pin "14") (pinfunction "~{RST}_14") (pintype "input"))
    )
    (net (code "82") (name "Net-(U2-VD)") (class "Default")
      (node (ref "C3") (pin "1") (pinfunction "1_1") (pintype "passive"))
      (node (ref "C4") (pin "1") (pinfunction "1_1") (pintype "passive"))
      (node (ref "R7") (pin "2") (pinfunction "2_2") (pintype "passive"))
      (node (ref "U2") (pin "13") (pinfunction "VD_13") (pintype "power_in"))
    )
    (net (code "83") (name "unconnected-(J4-NC-Pad7)") (class "Default")
      (node (ref "J4") (pin "7") (pinfunction "NC_7") (pintype "input+no_connect"))
    )
    (net (code "84") (name "unconnected-(J4-NC-Pad9)") (class "Default")
      (node (ref "J4") (pin "9") (pinfunction "NC_9") (pintype "input+no_connect"))
    )
    (net (code "85") (name "unconnected-(J4-TDI-Pad8)") (class "Default")
      (node (ref "J4") (pin "8") (pinfunction "TDI_8") (pintype "input+no_connect"))
    )
    (net (code "86") (name "unconnected-(U1B-PA0-Pad22)") (class "Default")
      (node (ref "U1") (pin "22") (pinfunction "PA0_22") (pintype "bidirectional"))
    )
    (net (code "87") (name "unconnected-(U1B-PA1-Pad23)") (class "Default")
      (node (ref "U1") (pin "23") (pinfunction "PA1_23") (pintype "bidirectional"))
    )
    (net (code "88") (name "unconnected-(U1B-PA2-Pad24)") (class "Default")
      (node (ref "U1") (pin "24") (pinfunction "PA2_24") (pintype "bidirectional"))
    )
    (net (code "89") (name "unconnected-(U1B-PA3-Pad25)") (class "Default")
      (node (ref "U1") (pin "25") (pinfunction "PA3_25") (pintype "bidirectional"))
    )
    (net (code "90") (name "unconnected-(U1B-PA8-Pad67)") (class "Default")
      (node (ref "U1") (pin "67") (pinfunction "PA8_67") (pintype "bidirectional"))
    )
    (net (code "91") (name "unconnected-(U1B-PA9-Pad68)") (class "Default")
      (node (ref "U1") (pin "68") (pinfunction "PA9_68") (pintype "bidirectional"))
    )
    (net (code "92") (name "unconnected-(U1B-PA10-Pad69)") (class "Default")
      (node (ref "U1") (pin "69") (pinfunction "PA10_69") (pintype "bidirectional"))
    )
    (net (code "93") (name "unconnected-(U1B-PA11-Pad70)") (class "Default")
      (node (ref "U1") (pin "70") (pinfunction "PA11_70") (pintype "bidirectional"))
    )
    (net (code "94") (name "unconnected-(U1B-PA12-Pad71)") (class "Default")
      (node (ref "U1") (pin "71") (pinfunction "PA12_71") (pintype "bidirectional"))
    )
    (net (code "95") (name "unconnected-(U1B-PB0-Pad34)") (class "Default")
      (node (ref "U1") (pin "34") (pinfunction "PB0_34") (pintype "bidirectional"))
    )
    (net (code "96") (name "unconnected-(U1B-PB1-Pad35)") (class "Default")
      (node (ref "U1") (pin "35") (pinfunction "PB1_35") (pintype "bidirectional"))
    )
    (net (code "97") (name "unconnected-(U1B-PB2-Pad36)") (class "Default")
      (node (ref "U1") (pin "36") (pinfunction "PB2_36") (pintype "bidirectional"))
    )
    (net (code "98") (name "unconnected-(U1B-PB4-Pad90)") (class "Default")
      (node (ref "U1") (pin "90") (pinfunction "PB4_90") (pintype "bidirectional"))
    )
    (net (code "99") (name "unconnected-(U1B-PB5-Pad91)") (class "Default")
      (node (ref "U1") (pin "91") (pinfunction "PB5_91") (pintype "bidirectional"))
    )
    (net (code "100") (name "unconnected-(U1B-PB6-Pad92)") (class "Default")
      (node (ref "U1") (pin "92") (pinfunction "PB6_92") (pintype "bidirectional"))
    )
    (net (code "101") (name "unconnected-(U1B-PB7-Pad93)") (class "Default")
      (node (ref "U1") (pin "93") (pinfunction "PB7_93") (pintype "bidirectional"))
    )
    (net (code "102") (name "unconnected-(U1B-PB8-Pad95)") (class "Default")
      (node (ref "U1") (pin "95") (pinfunction "PB8_95") (pintype "bidirectional"))
    )
    (net (code "103") (name "unconnected-(U1B-PB9-Pad96)") (class "Default")
      (node (ref "U1") (pin "96") (pinfunction "PB9_96") (pintype "bidirectional"))
    )
    (net (code "104") (name "unconnected-(U1B-PB10-Pad46)") (class "Default")
      (node (ref "U1") (pin "46") (pinfunction "PB10_46") (pintype "bidirectional"))
    )
    (net (code "105") (name "unconnected-(U1B-PB11-Pad47)") (class "Default")
      (node (ref "U1") (pin "47") (pinfunction "PB11_47") (pintype "bidirectional"))
    )
    (net (code "106") (name "unconnected-(U1B-PC0-Pad15)") (class "Default")
      (node (ref "U1") (pin "15") (pinfunction "PC0_15") (pintype "bidirectional"))
    )
    (net (code "107") (name "unconnected-(U1B-PC1-Pad16)") (class "Default")
      (node (ref "U1") (pin "16") (pinfunction "PC1_16") (pintype "bidirectional"))
    )
    (net (code "108") (name "unconnected-(U1B-PC2_C-Pad17)") (class "Default")
      (node (ref "U1") (pin "17") (pinfunction "PC2_C_17") (pintype "bidirectional"))
    )
    (net (code "109") (name "unconnected-(U1B-PC3_C-Pad18)") (class "Default")
      (node (ref "U1") (pin "18") (pinfunction "PC3_C_18") (pintype "bidirectional"))
    )
    (net (code "110") (name "unconnected-(U1B-PC4-Pad32)") (class "Default")
      (node (ref "U1") (pin "32") (pinfunction "PC4_32") (pintype "bidirectional"))
    )
    (net (code "111") (name "unconnected-(U1B-PC5-Pad33)") (class "Default")
      (node (ref "U1") (pin "33") (pinfunction "PC5_33") (pintype "bidirectional"))
    )
    (net (code "112") (name "unconnected-(U1B-PC6-Pad63)") (class "Default")
      (node (ref "U1") (pin "63") (pinfunction "PC6_63") (pintype "bidirectional"))
    )
    (net (code "113") (name "unconnected-(U1B-PC7-Pad64)") (class "Default")
      (node (ref "U1") (pin "64") (pinfunction "PC7_64") (pintype "bidirectional"))
    )
    (net (code "114") (name "unconnected-(U1B-PC8-Pad65)") (class "Default")
      (node (ref "U1") (pin "65") (pinfunction "PC8_65") (pintype "bidirectional"))
    )
    (net (code "115") (name "unconnected-(U1B-PC9-Pad66)") (class "Default")
      (node (ref "U1") (pin "66") (pinfunction "PC9_66") (pintype "bidirectional"))
    )
    (net (code "116") (name "unconnected-(U1B-PC13-Pad7)") (class "Default")
      (node (ref "U1") (pin "7") (pinfunction "PC13_7") (pintype "bidirectional"))
    )
    (net (code "117") (name "unconnected-(U1B-PD2-Pad83)") (class "Default")
      (node (ref "U1") (pin "83") (pinfunction "PD2_83") (pintype "bidirectional"))
    )
    (net (code "118") (name "unconnected-(U1B-PD3-Pad84)") (class "Default")
      (node (ref "U1") (pin "84") (pinfunction "PD3_84") (pintype "bidirectional"))
    )
    (net (code "119") (name "unconnected-(U1B-PD5-Pad86)") (class "Default")
      (node (ref "U1") (pin "86") (pinfunction "PD5_86") (pintype "bidirectional"))
    )
    (net (code "120") (name "unconnected-(U1B-PD6-Pad87)") (class "Default")
      (node (ref "U1") (pin "87") (pinfunction "PD6_87") (pintype "bidirectional"))
    )
    (net (code "121") (name "unconnected-(U1B-PD7-Pad88)") (class "Default")
      (node (ref "U1") (pin "88") (pinfunction "PD7_88") (pintype "bidirectional"))
    )
    (net (code "122") (name "unconnected-(U1B-PD8-Pad55)") (class "Default")
      (node (ref "U1") (pin "55") (pinfunction "PD8_55") (pintype "bidirectional"))
    )
    (net (code "123") (name "unconnected-(U1B-PD9-Pad56)") (class "Default")
      (node (ref "U1") (pin "56") (pinfunction "PD9_56") (pintype "bidirectional"))
    )
    (net (code "124") (name "unconnected-(U1B-PD10-Pad57)") (class "Default")
      (node (ref "U1") (pin "57") (pinfunction "PD10_57") (pintype "bidirectional"))
    )
    (net (code "125") (name "unconnected-(U1B-PD11-Pad58)") (class "Default")
      (node (ref "U1") (pin "58") (pinfunction "PD11_58") (pintype "bidirectional"))
    )
    (net (code "126") (name "unconnected-(U1B-PD12-Pad59)") (class "Default")
      (node (ref "U1") (pin "59") (pinfunction "PD12_59") (pintype "bidirectional"))
    )
    (net (code "127") (name "unconnected-(U1B-PD13-Pad60)") (class "Default")
      (node (ref "U1") (pin "60") (pinfunction "PD13_60") (pintype "bidirectional"))
    )
    (net (code "128") (name "unconnected-(U1B-PD14-Pad61)") (class "Default")
      (node (ref "U1") (pin "61") (pinfunction "PD14_61") (pintype "bidirectional"))
    )
    (net (code "129") (name "unconnected-(U1B-PD15-Pad62)") (class "Default")
      (node (ref "U1") (pin "62") (pinfunction "PD15_62") (pintype "bidirectional"))
    )
    (net (code "130") (name "unconnected-(U1B-PE0-Pad97)") (class "Default")
      (node (ref "U1") (pin "97") (pinfunction "PE0_97") (pintype "bidirectional"))
    )
    (net (code "131") (name "unconnected-(U1B-PE1-Pad98)") (class "Default")
      (node (ref "U1") (pin "98") (pinfunction "PE1_98") (pintype "bidirectional"))
    )
    (net (code "132") (name "unconnected-(U1B-PE2-Pad1)") (class "Default")
      (node (ref "U1") (pin "1") (pinfunction "PE2_1") (pintype "bidirectional"))
    )
    (net (code "133") (name "unconnected-(U1B-PE3-Pad2)") (class "Default")
      (node (ref "U1") (pin "2") (pinfunction "PE3_2") (pintype "bidirectional"))
    )
    (net (code "134") (name "unconnected-(U1B-PE4-Pad3)") (class "Default")
      (node (ref "U1") (pin "3") (pinfunction "PE4_3") (pintype "bidirectional"))
    )
    (net (code "135") (name "unconnected-(U1B-PE5-Pad4)") (class "Default")
      (node (ref "U1") (pin "4") (pinfunction "PE5_4") (pintype "bidirectional"))
    )
    (net (code "136") (name "unconnected-(U1B-PE6-Pad5)") (class "Default")
      (node (ref "U1") (pin "5") (pinfunction "PE6_5") (pintype "bidirectional"))
    )
    (net (code "137") (name "unconnected-(U1B-PE7-Pad37)") (class "Default")
      (node (ref "U1") (pin "37") (pinfunction "PE7_37") (pintype "bidirectional"))
    )
    (net (code "138") (name "unconnected-(U1B-PE8-Pad38)") (class "Default")
      (node (ref "U1") (pin "38") (pinfunction "PE8_38") (pintype "bidirectional"))
    )
    (net (code "139") (name "unconnected-(U1B-PE9-Pad39)") (class "Default")
      (node (ref "U1") (pin "39") (pinfunction "PE9_39") (pintype "bidirectional"))
    )
    (net (code "140") (name "unconnected-(U1B-PE10-Pad40)") (class "Default")
      (node (ref "U1") (pin "40") (pinfunction "PE10_40") (pintype "bidirectional"))
    )
    (net (code "141") (name "unconnected-(U1B-PE15-Pad45)") (class "Default")
      (node (ref "U1") (pin "45") (pinfunction "PE15_45") (pintype "bidirectional"))
    )
  )
)
